# wled-tube.net
KiCad netlist of a schematic drawn in Altium Designer
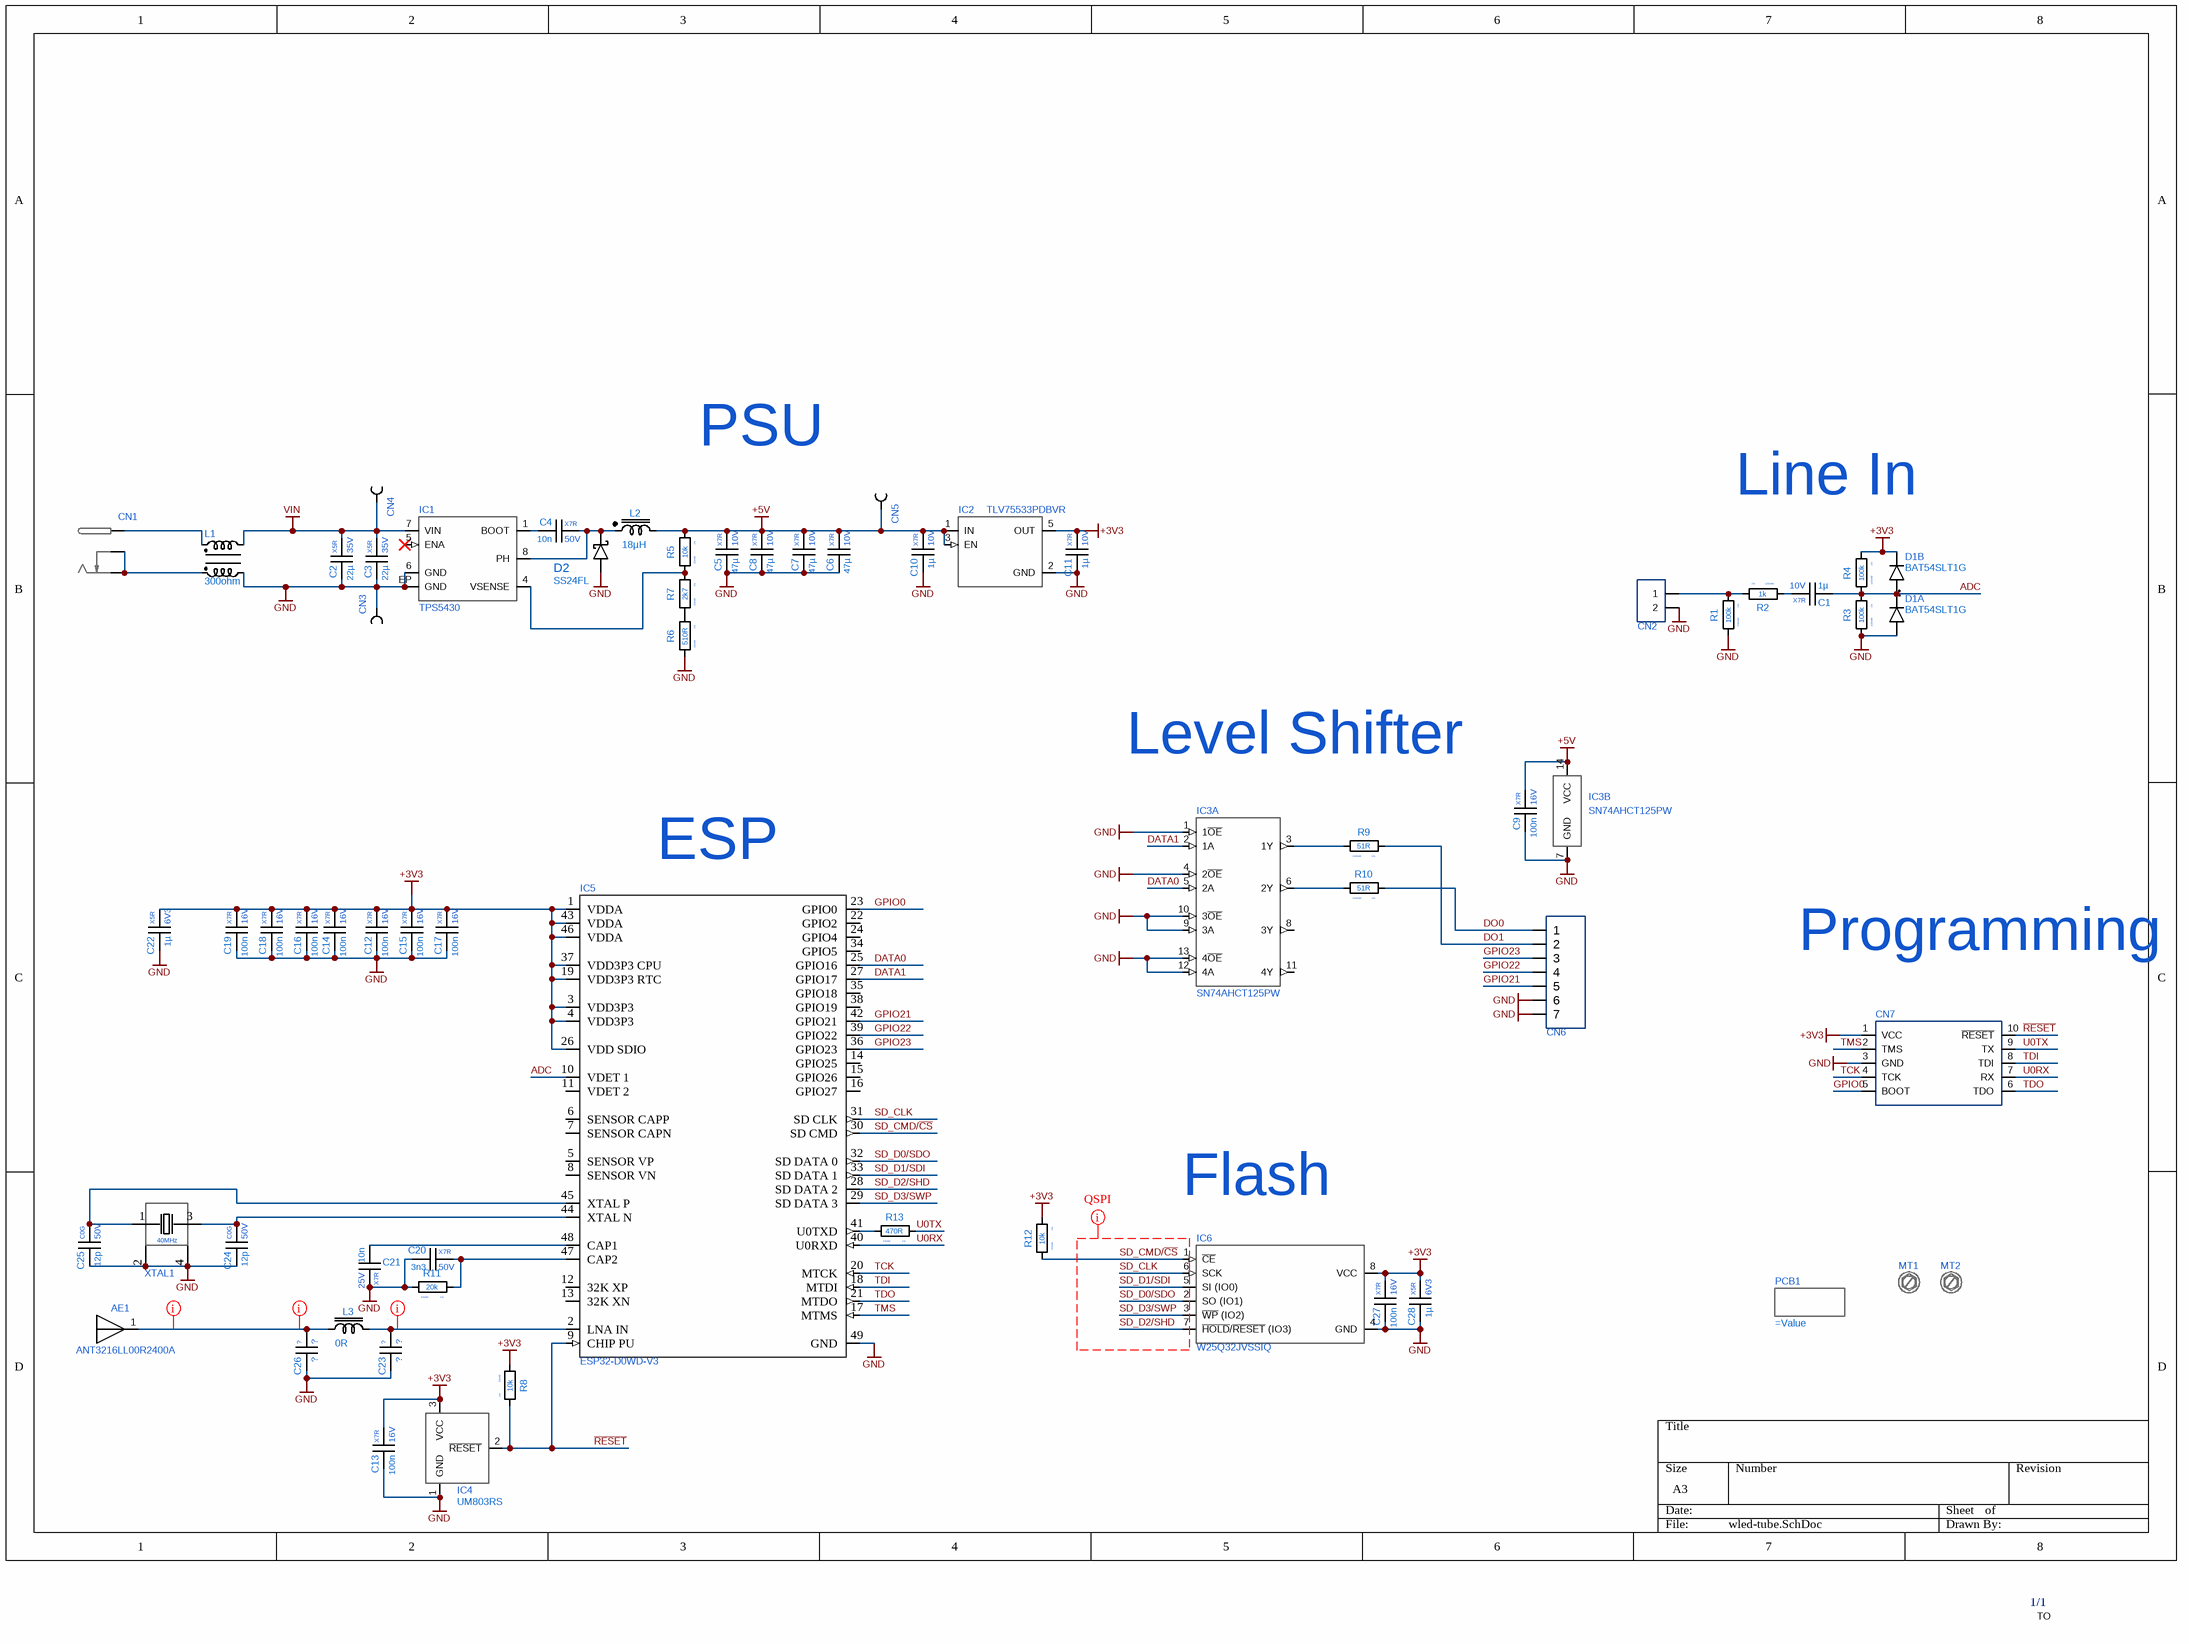
[diagram p0: wled-tube.SchDoc]

(export (version "E")
  (design (tool "Eeschema 10.0.6"))
  (components
    (comp (ref "AE1")
      (value "ANT3216LL00R2400A")
      (footprint "1206-ANT")
      (description "Ceramic chip antenna 2.4 GHz")
      (fields (field (name "MANUFACTURER") "Yageo"))
      (libsource (lib "RASE") (part "ANTENNA"))
    )
    (comp (ref "C1")
      (value "1µ")
      (footprint "0603-CAP")
      (description "CAP 0603 CERAMIC 1µ 10V ±10% X7R")
      (fields
        (field (name "_P2") "X7R")
        (field (name "_P1") "10V")
        (field (name "VOLTAGE") "10V")
        (field (name "TOLERANCE") "10%")
        (field (name "LIBRARY PATH") "NONPCAP.SchLib")
      )
      (libsource (lib "CDB") (part "NONPCAP"))
    )
    (comp (ref "C2")
      (value "22µ")
      (footprint "1210-CAP")
      (description "CAP 1210 CERAMIC 22µ 35V ±10% X5R")
      (fields
        (field (name "_P2") "X5R")
        (field (name "_P1") "35V")
        (field (name "VOLTAGE") "35V")
        (field (name "TOLERANCE") "10%")
        (field (name "LIBRARY PATH") "NONPCAP.SchLib")
      )
      (libsource (lib "CDB") (part "NONPCAP"))
    )
    (comp (ref "C3")
      (value "22µ")
      (footprint "1210-CAP")
      (description "CAP 1210 CERAMIC 22µ 35V ±10% X5R")
      (fields
        (field (name "_P2") "X5R")
        (field (name "_P1") "35V")
        (field (name "VOLTAGE") "35V")
        (field (name "TOLERANCE") "10%")
        (field (name "LIBRARY PATH") "NONPCAP.SchLib")
      )
      (libsource (lib "CDB") (part "NONPCAP"))
    )
    (comp (ref "C4")
      (value "10n")
      (footprint "0603-CAP")
      (description "CAP 0603 CERAMIC 10n 50V ±10% X7R")
      (fields
        (field (name "_P2") "X7R")
        (field (name "_P1") "50V")
        (field (name "VOLTAGE") "50V")
        (field (name "TOLERANCE") "10%")
        (field (name "LIBRARY PATH") "NONPCAP.SchLib")
      )
      (libsource (lib "CDB") (part "NONPCAP"))
    )
    (comp (ref "C5")
      (value "47µ")
      (footprint "1210-CAP")
      (description "CAP 1210 CERAMIC 47µ 10V ±10% X7R")
      (fields
        (field (name "_P2") "X7R")
        (field (name "_P1") "10V")
        (field (name "VOLTAGE") "10V")
        (field (name "TOLERANCE") "10%")
        (field (name "LIBRARY PATH") "NONPCAP.SchLib")
      )
      (libsource (lib "CDB") (part "NONPCAP"))
    )
    (comp (ref "C6")
      (value "47µ")
      (footprint "1210-CAP")
      (description "CAP 1210 CERAMIC 47µ 10V ±10% X7R")
      (fields
        (field (name "_P2") "X7R")
        (field (name "_P1") "10V")
        (field (name "VOLTAGE") "10V")
        (field (name "TOLERANCE") "10%")
        (field (name "LIBRARY PATH") "NONPCAP.SchLib")
      )
      (libsource (lib "CDB") (part "NONPCAP"))
    )
    (comp (ref "C7")
      (value "47µ")
      (footprint "1210-CAP")
      (description "CAP 1210 CERAMIC 47µ 10V ±10% X7R")
      (fields
        (field (name "_P2") "X7R")
        (field (name "_P1") "10V")
        (field (name "VOLTAGE") "10V")
        (field (name "TOLERANCE") "10%")
        (field (name "LIBRARY PATH") "NONPCAP.SchLib")
      )
      (libsource (lib "CDB") (part "NONPCAP"))
    )
    (comp (ref "C8")
      (value "47µ")
      (footprint "1210-CAP")
      (description "CAP 1210 CERAMIC 47µ 10V ±10% X7R")
      (fields
        (field (name "_P2") "X7R")
        (field (name "_P1") "10V")
        (field (name "VOLTAGE") "10V")
        (field (name "TOLERANCE") "10%")
        (field (name "LIBRARY PATH") "NONPCAP.SchLib")
      )
      (libsource (lib "CDB") (part "NONPCAP"))
    )
    (comp (ref "C9")
      (value "100n")
      (footprint "0402-CAP")
      (description "CAP 0402 CERAMIC 100n 16V ±10% X7R")
      (fields
        (field (name "_P2") "X7R")
        (field (name "_P1") "16V")
        (field (name "TOLERANCE") "10%")
        (field (name "VOLTAGE") "16V")
        (field (name "LIBRARY PATH") "NONPCAP.SchLib")
      )
      (libsource (lib "CDB") (part "NONPCAP"))
    )
    (comp (ref "C10")
      (value "1µ")
      (footprint "0603-CAP")
      (description "CAP 0603 CERAMIC 1µ 10V ±10% X7R")
      (fields
        (field (name "_P2") "X7R")
        (field (name "_P1") "10V")
        (field (name "VOLTAGE") "10V")
        (field (name "TOLERANCE") "10%")
        (field (name "LIBRARY PATH") "NONPCAP.SchLib")
      )
      (libsource (lib "CDB") (part "NONPCAP"))
    )
    (comp (ref "C11")
      (value "1µ")
      (footprint "0603-CAP")
      (description "CAP 0603 CERAMIC 1µ 10V ±10% X7R")
      (fields
        (field (name "_P2") "X7R")
        (field (name "_P1") "10V")
        (field (name "VOLTAGE") "10V")
        (field (name "TOLERANCE") "10%")
        (field (name "LIBRARY PATH") "NONPCAP.SchLib")
      )
      (libsource (lib "CDB") (part "NONPCAP"))
    )
    (comp (ref "C12")
      (value "100n")
      (footprint "0402-CAP")
      (description "CAP 0402 CERAMIC 100n 16V ±10% X7R")
      (fields
        (field (name "_P2") "X7R")
        (field (name "_P1") "16V")
        (field (name "TOLERANCE") "10%")
        (field (name "VOLTAGE") "16V")
        (field (name "LIBRARY PATH") "NONPCAP.SchLib")
      )
      (libsource (lib "CDB") (part "NONPCAP"))
    )
    (comp (ref "C13")
      (value "100n")
      (footprint "0402-CAP")
      (description "CAP 0402 CERAMIC 100n 16V ±10% X7R")
      (fields
        (field (name "_P2") "X7R")
        (field (name "_P1") "16V")
        (field (name "TOLERANCE") "10%")
        (field (name "VOLTAGE") "16V")
        (field (name "LIBRARY PATH") "NONPCAP.SchLib")
      )
      (libsource (lib "CDB") (part "NONPCAP"))
    )
    (comp (ref "C14")
      (value "100n")
      (footprint "0402-CAP")
      (description "CAP 0402 CERAMIC 100n 16V ±10% X7R")
      (fields
        (field (name "_P2") "X7R")
        (field (name "_P1") "16V")
        (field (name "TOLERANCE") "10%")
        (field (name "VOLTAGE") "16V")
        (field (name "LIBRARY PATH") "NONPCAP.SchLib")
      )
      (libsource (lib "CDB") (part "NONPCAP"))
    )
    (comp (ref "C15")
      (value "100n")
      (footprint "0402-CAP")
      (description "CAP 0402 CERAMIC 100n 16V ±10% X7R")
      (fields
        (field (name "_P2") "X7R")
        (field (name "_P1") "16V")
        (field (name "TOLERANCE") "10%")
        (field (name "VOLTAGE") "16V")
        (field (name "LIBRARY PATH") "NONPCAP.SchLib")
      )
      (libsource (lib "CDB") (part "NONPCAP"))
    )
    (comp (ref "C16")
      (value "100n")
      (footprint "0402-CAP")
      (description "CAP 0402 CERAMIC 100n 16V ±10% X7R")
      (fields
        (field (name "_P2") "X7R")
        (field (name "_P1") "16V")
        (field (name "TOLERANCE") "10%")
        (field (name "VOLTAGE") "16V")
        (field (name "LIBRARY PATH") "NONPCAP.SchLib")
      )
      (libsource (lib "CDB") (part "NONPCAP"))
    )
    (comp (ref "C17")
      (value "100n")
      (footprint "0402-CAP")
      (description "CAP 0402 CERAMIC 100n 16V ±10% X7R")
      (fields
        (field (name "_P2") "X7R")
        (field (name "_P1") "16V")
        (field (name "TOLERANCE") "10%")
        (field (name "VOLTAGE") "16V")
        (field (name "LIBRARY PATH") "NONPCAP.SchLib")
      )
      (libsource (lib "CDB") (part "NONPCAP"))
    )
    (comp (ref "C18")
      (value "100n")
      (footprint "0402-CAP")
      (description "CAP 0402 CERAMIC 100n 16V ±10% X7R")
      (fields
        (field (name "_P2") "X7R")
        (field (name "_P1") "16V")
        (field (name "TOLERANCE") "10%")
        (field (name "VOLTAGE") "16V")
        (field (name "LIBRARY PATH") "NONPCAP.SchLib")
      )
      (libsource (lib "CDB") (part "NONPCAP"))
    )
    (comp (ref "C19")
      (value "100n")
      (footprint "0402-CAP")
      (description "CAP 0402 CERAMIC 100n 16V ±10% X7R")
      (fields
        (field (name "_P2") "X7R")
        (field (name "_P1") "16V")
        (field (name "TOLERANCE") "10%")
        (field (name "VOLTAGE") "16V")
        (field (name "LIBRARY PATH") "NONPCAP.SchLib")
      )
      (libsource (lib "CDB") (part "NONPCAP"))
    )
    (comp (ref "C20")
      (value "3n3")
      (footprint "0402-CAP")
      (description "Cap SMT 0402 3n3 50V X7R ±10%")
      (fields
        (field (name "_P2") "X7R")
        (field (name "_P1") "50V")
        (field (name "VOLTAGE") "50V")
        (field (name "TOLERANCE") "10%")
      )
      (libsource (lib "RASE") (part "NPCAP"))
    )
    (comp (ref "C21")
      (value "10n")
      (footprint "0402-CAP")
      (description "Cap SMT 0402 10n 25V X7R ±10%")
      (fields
        (field (name "VOLTAGE") "25V")
        (field (name "TOLERANCE") "10%")
        (field (name "_P2") "X7R")
        (field (name "_P1") "25V")
      )
      (libsource (lib "RASE") (part "NPCAP"))
    )
    (comp (ref "C22")
      (value "1µ")
      (footprint "0402-CAP")
      (description "CAP 0402 CERAMIC 1µ 6V3 ±10% X5R")
      (fields
        (field (name "_P2") "X5R")
        (field (name "_P1") "6V3")
        (field (name "TOLERANCE") "10%")
        (field (name "VOLTAGE") "6V3")
        (field (name "LIBRARY PATH") "NONPCAP.SchLib")
      )
      (libsource (lib "CDB") (part "NONPCAP"))
    )
    (comp (ref "C23")
      (value "?")
      (footprint "0402-CAP")
      (description "Cap SMT 0402 ? ? ? ±?%")
      (fields (field (name "_P2") "?") (field (name "_P1") "?") (field (name "TOLERANCE") "?%"))
      (libsource (lib "RASE") (part "NPCAP"))
    )
    (comp (ref "C24")
      (value "12p")
      (footprint "0402-CAP")
      (description "Cap SMT 0402 12p 50V C0G ±5%")
      (fields
        (field (name "_P2") "C0G")
        (field (name "_P1") "50V")
        (field (name "VOLTAGE") "50V")
        (field (name "TOLERANCE") "5%")
      )
      (libsource (lib "RASE") (part "NPCAP"))
    )
    (comp (ref "C25")
      (value "12p")
      (footprint "0402-CAP")
      (description "Cap SMT 0402 12p 50V C0G ±5%")
      (fields
        (field (name "_P2") "C0G")
        (field (name "_P1") "50V")
        (field (name "VOLTAGE") "50V")
        (field (name "TOLERANCE") "5%")
      )
      (libsource (lib "RASE") (part "NPCAP"))
    )
    (comp (ref "C26")
      (value "?")
      (footprint "0402-CAP")
      (description "Cap SMT 0402 ? ? ? ±?%")
      (fields (field (name "_P2") "?") (field (name "_P1") "?") (field (name "TOLERANCE") "?%"))
      (libsource (lib "RASE") (part "NPCAP"))
    )
    (comp (ref "C27")
      (value "100n")
      (footprint "0402-CAP")
      (description "CAP 0402 CERAMIC 100n 16V ±10% X7R")
      (fields
        (field (name "_P2") "X7R")
        (field (name "_P1") "16V")
        (field (name "TOLERANCE") "10%")
        (field (name "VOLTAGE") "16V")
        (field (name "LIBRARY PATH") "NONPCAP.SchLib")
      )
      (libsource (lib "CDB") (part "NONPCAP"))
    )
    (comp (ref "C28")
      (value "1µ")
      (footprint "0402-CAP")
      (description "CAP 0402 CERAMIC 1µ 6V3 ±10% X5R")
      (fields
        (field (name "_P2") "X5R")
        (field (name "_P1") "6V3")
        (field (name "TOLERANCE") "10%")
        (field (name "VOLTAGE") "6V3")
        (field (name "LIBRARY PATH") "NONPCAP.SchLib")
      )
      (libsource (lib "CDB") (part "NONPCAP"))
    )
    (comp (ref "CN1")
      (value "~")
      (footprint "DCJACK-1")
      (description "DC Jack Lih Sheng LD-0202A 2.0mm")
      (fields
        (field (name "MANUFACTURER") "Lih Sheng")
        (field (name "MANUFACTURER PART NUMBER") "LD-0202A-2.0")
      )
      (libsource (lib "CDB") (part "DCJACK-1"))
    )
    (comp (ref "CN2")
      (value "CON-HDR-MALE-2.54MM-1x2-VERT-THT")
      (footprint "CON-HDR-MALE-2.54MM-1x2-VERT-THT")
      (description "CONN HEADER VERT 2POS 2.54MM")
      (fields
        (field (name "MANUFACTURER PART NUMBER") "TSW-102-07-L-S")
        (field (name "MANUFACTURER") "Samtec Inc.")
      )
      (libsource (lib "CDB") (part "CON-1x2"))
    )
    (comp (ref "CN3") (value "PAD1.3MM") (footprint "PAD1MM3") (libsource (lib "CDB") (part "PAD1.3MM")))
    (comp (ref "CN4") (value "PAD1.3MM") (footprint "PAD1MM3") (libsource (lib "CDB") (part "PAD1.3MM")))
    (comp (ref "CN5") (value "PAD1.3MM") (footprint "PAD1MM3") (libsource (lib "CDB") (part "PAD1.3MM")))
    (comp (ref "CN6")
      (value "CON-HDR-MALE-2.54MM-1x7-VERT-THT")
      (footprint "CON-HDR-MALE-2.54MM-1x7-VERT-THT")
      (description "CONN HEADER VERT 7POS 2.54MM")
      (fields
        (field (name "MANUFACTURER PART NUMBER") "TSW-107-07-L-S")
        (field (name "MANUFACTURER") "Samtec Inc.")
      )
      (libsource (lib "CDB") (part "CON-1x7"))
    )
    (comp (ref "CN7")
      (value "TC2050_RASE")
      (footprint "TC2050")
      (description "Solderless programming connector, mates with Tag-Connect TC2050")
      (libsource (lib "RASE") (part "TC2050_RASE"))
    )
    (comp (ref "D1")
      (value "BAT54SLT1G")
      (footprint "SOT-23")
      (description "BAT54SLT1G Dual 30V 200mA Schottky Diode")
      (fields (field (name "MANUFACTURER") "ON Semiconductor"))
      (libsource (lib "CDB") (part "BAT54SLT1G"))
    )
    (comp (ref "D2")
      (value "SS24FL")
      (footprint "SMAF")
      (description "40V 550mV@2A 2A SMAF Schottky Barrier Diodes (SBD) ROHS")
      (fields (field (name "MANUFACTURER") "Shikues"))
      (libsource (lib "RASE") (part "DiodeS"))
    )
    (comp (ref "IC1")
      (value "TPS5430")
      (footprint "TPS5430")
      (description "Step-down type SO-8 DC-DC Converters ROHS")
      (fields (field (name "MANUFACTURER PART NUMBER") "TPS5430DDAR") (field (name "MANUFACTURER") "TI"))
      (libsource (lib "RASE") (part "TPS5430"))
    )
    (comp (ref "IC2")
      (value "TLV75533PDBVR")
      (footprint "SOT-23-5")
      (fields (field (name "MANUFACTURER") "TI"))
      (libsource (lib "CDB") (part "DS8241-33S5"))
    )
    (comp (ref "IC3")
      (value "SN74AHCT125PW")
      (footprint "TSSOP14")
      (description "Quad buffer, TSSOP14")
      (fields
        (field (name "MANUFACTURER") "Texas Instruments")
        (field (name "MANUFACTURER PART NUMBER") "SN74AHCT125PWR")
      )
      (libsource (lib "CDB") (part "74AHCT125PW"))
    )
    (comp (ref "IC4")
      (value "UM803RS")
      (footprint "SOT-23")
      (description "MICROPROCESSOR RESET CIRCUIT 2.63V SOT23")
      (libsource (lib "CDB") (part "UM803RS"))
    )
    (comp (ref "IC5")
      (value "ESP32-D0WD-V3")
      (footprint "ESP32-D0WD-V3")
      (fields (field (name "MANUFACTURER") "Espressif"))
      (libsource (lib "RASE") (part "ESP32-D0WD-V3"))
    )
    (comp (ref "IC6")
      (value "W25Q32JVSSIQ")
      (footprint "SO-08L")
      (description "3V 32M-BIT SERIAL FLASH MEMORY WITH DUAL/QUAD SPI, QPI & DTR")
      (fields (field (name "MANUFACTURER") "Winbond"))
      (libsource (lib "CDB") (part "IS25LP032D-JBLE"))
    )
    (comp (ref "L1")
      (value "300ohm")
      (footprint "COILCMACM7060")
      (description "TDK ACM7060 / Sunltech Tech SMW7060 / Shun Xiang Nuo Elec SMCM7060")
      (fields
        (field (name "MANUFACTURER") "TDK, Sunltech, Shun Xiang Nuo Elec")
        (field (name "MANUFACTURER PART NUMBER") "ACM7060-301-2PL-TL01, SMW7060S301NTT, SMCM7060-301T")
      )
      (libsource (lib "CDB") (part "COILCM7060-"))
    )
    (comp (ref "L2")
      (value "18µH")
      (footprint "COILSRN8040")
      (description "18uH, 68mOhm(max), 2.7A(sat), 2.4A(DC)")
      (fields (field (name "MANUFACTURER") "SXN") (field (name "MANUFACTURER PART NUMBER") "SMNR8040-180MT"))
      (libsource (lib "CDB") (part "COIL_DOTTED"))
    )
    (comp (ref "L3")
      (value "0R")
      (footprint "0402-IND")
      (description "Inductor SMT ? ±?%")
      (fields (field (name "TOLERANCE") "?%"))
      (libsource (lib "RASE") (part "COIL"))
    )
    (comp (ref "MT1") (value "*") (footprint "SCRW3MM") (libsource (lib "CDB") (part "SCRW-3MMISO")))
    (comp (ref "MT2") (value "*") (footprint "SCRW3MM") (libsource (lib "CDB") (part "SCRW-3MMISO")))
    (comp (ref "PCB1")
      (value "~")
      (footprint "PCB")
      (description "See PCB gerber files for specifications.")
      (libsource (lib "CDB") (part "PCB"))
    )
    (comp (ref "R1")
      (value "100k")
      (footprint "0603-RES")
      (description "RES SMD 100K OHM 1% 1/10W 0603")
      (fields
        (field (name "_P2") "1%")
        (field (name "_P1") "100mW")
        (field (name "MANUFACTURER PART NUMBER") "RC0603FR-07100KL")
        (field (name "MANUFACTURER") "Yageo")
      )
      (libsource (lib "CDB") (part "RES"))
    )
    (comp (ref "R2")
      (value "1k")
      (footprint "0603-RES")
      (description "RES SMD 1K OHM 1% 1/10W 0603")
      (fields
        (field (name "_P2") "1%")
        (field (name "_P1") "100mW")
        (field (name "MANUFACTURER PART NUMBER") "RC0603FR-071KL")
        (field (name "MANUFACTURER") "Yageo")
      )
      (libsource (lib "CDB") (part "RES"))
    )
    (comp (ref "R3")
      (value "100k")
      (footprint "0603-RES")
      (description "RES SMD 100K OHM 1% 1/10W 0603")
      (fields
        (field (name "_P2") "1%")
        (field (name "_P1") "100mW")
        (field (name "MANUFACTURER PART NUMBER") "RC0603FR-07100KL")
        (field (name "MANUFACTURER") "Yageo")
      )
      (libsource (lib "CDB") (part "RES"))
    )
    (comp (ref "R4")
      (value "100k")
      (footprint "0603-RES")
      (description "RES SMD 100K OHM 1% 1/10W 0603")
      (fields
        (field (name "_P2") "1%")
        (field (name "_P1") "100mW")
        (field (name "MANUFACTURER PART NUMBER") "RC0603FR-07100KL")
        (field (name "MANUFACTURER") "Yageo")
      )
      (libsource (lib "CDB") (part "RES"))
    )
    (comp (ref "R5")
      (value "10k")
      (footprint "0402-RES")
      (description "RES SMD 10K OHM 1% 1/16W 0402")
      (fields
        (field (name "_P2") "1%")
        (field (name "_P1") "63mW")
        (field (name "MANUFACTURER PART NUMBER") "RC0402FR-0710KL")
        (field (name "MANUFACTURER") "Yageo")
      )
      (libsource (lib "CDB") (part "RES"))
    )
    (comp (ref "R6")
      (value "510R")
      (footprint "0402-RES")
      (description "RES SMD 510 OHM 1% 1/16W 0402")
      (fields
        (field (name "_P2") "1%")
        (field (name "_P1") "63mW")
        (field (name "MANUFACTURER PART NUMBER") "RC0402FR-07510RL")
        (field (name "MANUFACTURER") "Yageo")
      )
      (libsource (lib "CDB") (part "RES"))
    )
    (comp (ref "R7")
      (value "2k7")
      (footprint "0402-RES")
      (description "RES SMD 2.7K OHM 1% 1/16W 0402")
      (fields
        (field (name "_P2") "1%")
        (field (name "_P1") "63mW")
        (field (name "MANUFACTURER PART NUMBER") "RC0402FR-072K7L")
        (field (name "MANUFACTURER") "Yageo")
      )
      (libsource (lib "CDB") (part "RES"))
    )
    (comp (ref "R8")
      (value "10k")
      (footprint "0402-RES")
      (description "RES SMD 10K OHM 1% 1/16W 0402")
      (fields
        (field (name "_P2") "1%")
        (field (name "_P1") "63mW")
        (field (name "MANUFACTURER PART NUMBER") "RC0402FR-0710KL")
        (field (name "MANUFACTURER") "Yageo")
      )
      (libsource (lib "") (part "RES_1"))
    )
    (comp (ref "R9")
      (value "51R")
      (footprint "0603-RES")
      (description "RES SMD 51 OHM 1% 1/10W 0603")
      (fields
        (field (name "_P2") "1%")
        (field (name "_P1") "100mW")
        (field (name "MANUFACTURER PART NUMBER") "RC0603FR-0751RL")
        (field (name "MANUFACTURER") "Yageo")
      )
      (libsource (lib "") (part "RES_1"))
    )
    (comp (ref "R10")
      (value "51R")
      (footprint "0603-RES")
      (description "RES SMD 51 OHM 1% 1/10W 0603")
      (fields
        (field (name "_P2") "1%")
        (field (name "_P1") "100mW")
        (field (name "MANUFACTURER PART NUMBER") "RC0603FR-0751RL")
        (field (name "MANUFACTURER") "Yageo")
      )
      (libsource (lib "") (part "RES_1"))
    )
    (comp (ref "R11")
      (value "20k")
      (footprint "0402-RES")
      (description "RES SMD 20K OHM 1% 1/16W 0402")
      (fields
        (field (name "_P2") "1%")
        (field (name "_P1") "63mW")
        (field (name "MANUFACTURER PART NUMBER") "RC0402FR-0720KL")
        (field (name "MANUFACTURER") "Yageo")
      )
      (libsource (lib "") (part "RES_1"))
    )
    (comp (ref "R12")
      (value "10k")
      (footprint "0402-RES")
      (description "RES SMD 10K OHM 1% 1/16W 0402")
      (fields
        (field (name "_P2") "1%")
        (field (name "_P1") "63mW")
        (field (name "MANUFACTURER PART NUMBER") "RC0402FR-0710KL")
        (field (name "MANUFACTURER") "Yageo")
      )
      (libsource (lib "CDB") (part "RES"))
    )
    (comp (ref "R13")
      (value "470R")
      (footprint "0402-RES")
      (description "RES SMD 470 OHM 1% 1/16W 0402")
      (fields
        (field (name "_P2") "1%")
        (field (name "_P1") "63mW")
        (field (name "MANUFACTURER PART NUMBER") "RC0402FR-07470RL")
        (field (name "MANUFACTURER") "Yageo")
      )
      (libsource (lib "") (part "RES_1"))
    )
    (comp (ref "XTAL1")
      (value "TSX-3225 40.0000MF10Y-K0")
      (footprint "TSX-3225")
      (description "CRYSTAL 40.0000MHZ 10PF SMD")
      (fields (field (name "FREQUENCY") "40MHz") (field (name "MANUFACTURER") "EPSON"))
      (libsource (lib "CDB") (part "TSX-3225"))
    )
  )
  (nets
    (net (code "1") (name "+3V3") (class "Default")
      (node (ref "C11") (pin "2") (pinfunction "2_2") (pintype "passive"))
      (node (ref "C12") (pin "2") (pinfunction "2_2") (pintype "passive"))
      (node (ref "C13") (pin "2") (pinfunction "2_2") (pintype "passive"))
      (node (ref "C14") (pin "2") (pinfunction "2_2") (pintype "passive"))
      (node (ref "C15") (pin "2") (pinfunction "2_2") (pintype "passive"))
      (node (ref "C16") (pin "2") (pinfunction "2_2") (pintype "passive"))
      (node (ref "C17") (pin "2") (pinfunction "2_2") (pintype "passive"))
      (node (ref "C18") (pin "2") (pinfunction "2_2") (pintype "passive"))
      (node (ref "C19") (pin "2") (pinfunction "2_2") (pintype "passive"))
      (node (ref "C22") (pin "2") (pinfunction "2_2") (pintype "passive"))
      (node (ref "C27") (pin "2") (pinfunction "2_2") (pintype "passive"))
      (node (ref "C28") (pin "2") (pinfunction "2_2") (pintype "passive"))
      (node (ref "CN7") (pin "1") (pinfunction "VCC_1") (pintype "passive"))
      (node (ref "D1") (pin "2") (pinfunction "K_2") (pintype "passive"))
      (node (ref "IC2") (pin "5") (pinfunction "OUT_5") (pintype "power_in"))
      (node (ref "IC4") (pin "3") (pinfunction "VCC_3") (pintype "passive"))
      (node (ref "IC5") (pin "1") (pinfunction "VDDA_1") (pintype "power_in"))
      (node (ref "IC5") (pin "19") (pinfunction "VDD3P3_RTC_19") (pintype "power_in"))
      (node (ref "IC5") (pin "26") (pinfunction "VDD_SDIO_26") (pintype "power_in"))
      (node (ref "IC5") (pin "3") (pinfunction "VDD3P3_3") (pintype "power_in"))
      (node (ref "IC5") (pin "37") (pinfunction "VDD3P3_CPU_37") (pintype "power_in"))
      (node (ref "IC5") (pin "4") (pinfunction "VDD3P3_4") (pintype "power_in"))
      (node (ref "IC5") (pin "43") (pinfunction "VDDA_43") (pintype "power_in"))
      (node (ref "IC5") (pin "46") (pinfunction "VDDA_46") (pintype "power_in"))
      (node (ref "IC6") (pin "8") (pinfunction "VCC_8") (pintype "power_in"))
      (node (ref "R12") (pin "2") (pinfunction "2_2") (pintype "passive"))
      (node (ref "R4") (pin "2") (pinfunction "2_2") (pintype "passive"))
      (node (ref "R8") (pin "1") (pinfunction "1_1") (pintype "passive"))
    )
    (net (code "2") (name "+5V") (class "Default")
      (node (ref "C10") (pin "2") (pinfunction "2_2") (pintype "passive"))
      (node (ref "C5") (pin "2") (pinfunction "2_2") (pintype "passive"))
      (node (ref "C6") (pin "2") (pinfunction "2_2") (pintype "passive"))
      (node (ref "C7") (pin "2") (pinfunction "2_2") (pintype "passive"))
      (node (ref "C8") (pin "2") (pinfunction "2_2") (pintype "passive"))
      (node (ref "C9") (pin "2") (pinfunction "2_2") (pintype "passive"))
      (node (ref "CN5") (pin "1") (pinfunction "1_1") (pintype "passive"))
      (node (ref "IC2") (pin "1") (pinfunction "IN_1") (pintype "power_in"))
      (node (ref "IC2") (pin "3") (pinfunction "EN_3") (pintype "input"))
      (node (ref "IC3") (pin "14") (pinfunction "VCC_14") (pintype "power_in"))
      (node (ref "L2") (pin "2") (pinfunction "2_2") (pintype "passive"))
      (node (ref "R5") (pin "2") (pinfunction "2_2") (pintype "passive"))
    )
    (net (code "3") (name "/ADC") (class "Default")
      (node (ref "C1") (pin "1") (pinfunction "1_1") (pintype "passive"))
      (node (ref "D1") (pin "3") (pinfunction "K_3") (pintype "passive"))
      (node (ref "IC5") (pin "10") (pinfunction "VDET_1_10") (pintype "power_in"))
      (node (ref "R3") (pin "2") (pinfunction "2_2") (pintype "passive"))
      (node (ref "R4") (pin "1") (pinfunction "1_1") (pintype "passive"))
    )
    (net (code "4") (name "/DATA0") (class "Default")
      (node (ref "IC3") (pin "5") (pinfunction "2A_5") (pintype "input"))
      (node (ref "IC5") (pin "25") (pinfunction "GPIO16_25") (pintype "bidirectional"))
    )
    (net (code "5") (name "/DATA1") (class "Default")
      (node (ref "IC3") (pin "2") (pinfunction "1A_2") (pintype "input"))
      (node (ref "IC5") (pin "27") (pinfunction "GPIO17_27") (pintype "bidirectional"))
    )
    (net (code "6") (name "/DO0") (class "Default")
      (node (ref "CN6") (pin "1") (pinfunction "1_1") (pintype "passive"))
      (node (ref "R10") (pin "2") (pinfunction "2_2") (pintype "passive"))
    )
    (net (code "7") (name "/DO1") (class "Default")
      (node (ref "CN6") (pin "2") (pinfunction "2_2") (pintype "passive"))
      (node (ref "R9") (pin "2") (pinfunction "2_2") (pintype "passive"))
    )
    (net (code "8") (name "/GPIO0") (class "Default")
      (node (ref "CN7") (pin "5") (pinfunction "BOOT_5") (pintype "passive"))
      (node (ref "IC5") (pin "23") (pinfunction "GPIO0_23") (pintype "bidirectional"))
    )
    (net (code "9") (name "/GPIO21") (class "Default")
      (node (ref "CN6") (pin "5") (pinfunction "5_5") (pintype "passive"))
      (node (ref "IC5") (pin "42") (pinfunction "GPIO21_42") (pintype "bidirectional"))
    )
    (net (code "10") (name "/GPIO22") (class "Default")
      (node (ref "CN6") (pin "4") (pinfunction "4_4") (pintype "passive"))
      (node (ref "IC5") (pin "39") (pinfunction "GPIO22_39") (pintype "bidirectional"))
    )
    (net (code "11") (name "/GPIO23") (class "Default")
      (node (ref "CN6") (pin "3") (pinfunction "3_3") (pintype "passive"))
      (node (ref "IC5") (pin "36") (pinfunction "GPIO23_36") (pintype "bidirectional"))
    )
    (net (code "12") (name "/SD_CLK") (class "Default")
      (node (ref "IC5") (pin "31") (pinfunction "SD_CLK_31") (pintype "output"))
      (node (ref "IC6") (pin "6") (pinfunction "SCK_6") (pintype "input"))
    )
    (net (code "13") (name "/SD_CMD{slash}~{CS}") (class "Default")
      (node (ref "IC5") (pin "30") (pinfunction "SD_CMD_30") (pintype "output"))
      (node (ref "IC6") (pin "1") (pinfunction "~{CE}_1") (pintype "input"))
      (node (ref "R12") (pin "1") (pinfunction "1_1") (pintype "passive"))
    )
    (net (code "14") (name "/SD_D0{slash}SDO") (class "Default")
      (node (ref "IC5") (pin "32") (pinfunction "SD_DATA_0_32") (pintype "output"))
      (node (ref "IC6") (pin "2") (pinfunction "SO_(IO1)_2") (pintype "bidirectional"))
    )
    (net (code "15") (name "/SD_D1{slash}SDI") (class "Default")
      (node (ref "IC5") (pin "33") (pinfunction "SD_DATA_1_33") (pintype "output"))
      (node (ref "IC6") (pin "5") (pinfunction "SI_(IO0)_5") (pintype "bidirectional"))
    )
    (net (code "16") (name "/SD_D2{slash}SHD") (class "Default")
      (node (ref "IC5") (pin "28") (pinfunction "SD_DATA_2_28") (pintype "bidirectional"))
      (node (ref "IC6") (pin "7") (pinfunction "~{HOLD}/~{RESET}_(IO3)_7") (pintype "bidirectional"))
    )
    (net (code "17") (name "/SD_D3{slash}SWP") (class "Default")
      (node (ref "IC5") (pin "29") (pinfunction "SD_DATA_3_29") (pintype "bidirectional"))
      (node (ref "IC6") (pin "3") (pinfunction "~{WP}_(IO2)_3") (pintype "bidirectional"))
    )
    (net (code "18") (name "/TCK") (class "Default")
      (node (ref "CN7") (pin "4") (pinfunction "TCK_4") (pintype "passive"))
      (node (ref "IC5") (pin "20") (pinfunction "MTCK_20") (pintype "input"))
    )
    (net (code "19") (name "/TDI") (class "Default")
      (node (ref "CN7") (pin "8") (pinfunction "TDI_8") (pintype "passive"))
      (node (ref "IC5") (pin "18") (pinfunction "MTDI_18") (pintype "input"))
    )
    (net (code "20") (name "/TDO") (class "Default")
      (node (ref "CN7") (pin "6") (pinfunction "TDO_6") (pintype "passive"))
      (node (ref "IC5") (pin "21") (pinfunction "MTDO_21") (pintype "output"))
    )
    (net (code "21") (name "/TMS") (class "Default")
      (node (ref "CN7") (pin "2") (pinfunction "TMS_2") (pintype "passive"))
      (node (ref "IC5") (pin "17") (pinfunction "MTMS_17") (pintype "input"))
    )
    (net (code "22") (name "/U0RX") (class "Default")
      (node (ref "CN7") (pin "7") (pinfunction "RX_7") (pintype "passive"))
      (node (ref "IC5") (pin "40") (pinfunction "U0RXD_40") (pintype "input"))
    )
    (net (code "23") (name "/U0TX") (class "Default")
      (node (ref "CN7") (pin "9") (pinfunction "TX_9") (pintype "passive"))
      (node (ref "R13") (pin "2") (pinfunction "2_2") (pintype "passive"))
    )
    (net (code "24") (name "/~{RESET}") (class "Default")
      (node (ref "CN7") (pin "10") (pinfunction "~{RESET}_10") (pintype "passive"))
      (node (ref "IC4") (pin "2") (pinfunction "RESET_2") (pintype "passive"))
      (node (ref "IC5") (pin "9") (pinfunction "CHIP_PU_9") (pintype "input"))
      (node (ref "R8") (pin "2") (pinfunction "2_2") (pintype "passive"))
    )
    (net (code "25") (name "GND") (class "Default")
      (node (ref "C10") (pin "1") (pinfunction "1_1") (pintype "passive"))
      (node (ref "C11") (pin "1") (pinfunction "1_1") (pintype "passive"))
      (node (ref "C12") (pin "1") (pinfunction "1_1") (pintype "passive"))
      (node (ref "C13") (pin "1") (pinfunction "1_1") (pintype "passive"))
      (node (ref "C14") (pin "1") (pinfunction "1_1") (pintype "passive"))
      (node (ref "C15") (pin "1") (pinfunction "1_1") (pintype "passive"))
      (node (ref "C16") (pin "1") (pinfunction "1_1") (pintype "passive"))
      (node (ref "C17") (pin "1") (pinfunction "1_1") (pintype "passive"))
      (node (ref "C18") (pin "1") (pinfunction "1_1") (pintype "passive"))
      (node (ref "C19") (pin "1") (pinfunction "1_1") (pintype "passive"))
      (node (ref "C2") (pin "1") (pinfunction "1_1") (pintype "passive"))
      (node (ref "C20") (pin "1") (pinfunction "1_1") (pintype "passive"))
      (node (ref "C21") (pin "2") (pinfunction "2_2") (pintype "passive"))
      (node (ref "C22") (pin "1") (pinfunction "1_1") (pintype "passive"))
      (node (ref "C23") (pin "1") (pinfunction "1_1") (pintype "passive"))
      (node (ref "C24") (pin "1") (pinfunction "1_1") (pintype "passive"))
      (node (ref "C25") (pin "1") (pinfunction "1_1") (pintype "passive"))
      (node (ref "C26") (pin "1") (pinfunction "1_1") (pintype "passive"))
      (node (ref "C27") (pin "1") (pinfunction "1_1") (pintype "passive"))
      (node (ref "C28") (pin "1") (pinfunction "1_1") (pintype "passive"))
      (node (ref "C3") (pin "1") (pinfunction "1_1") (pintype "passive"))
      (node (ref "C5") (pin "1") (pinfunction "1_1") (pintype "passive"))
      (node (ref "C6") (pin "1") (pinfunction "1_1") (pintype "passive"))
      (node (ref "C7") (pin "1") (pinfunction "1_1") (pintype "passive"))
      (node (ref "C8") (pin "1") (pinfunction "1_1") (pintype "passive"))
      (node (ref "C9") (pin "1") (pinfunction "1_1") (pintype "passive"))
      (node (ref "CN2") (pin "2") (pinfunction "2_2") (pintype "passive"))
      (node (ref "CN3") (pin "1") (pinfunction "1_1") (pintype "passive"))
      (node (ref "CN6") (pin "6") (pinfunction "6_6") (pintype "passive"))
      (node (ref "CN6") (pin "7") (pinfunction "7_7") (pintype "passive"))
      (node (ref "CN7") (pin "3") (pinfunction "GND_3") (pintype "passive"))
      (node (ref "D1") (pin "1") (pinfunction "A_1") (pintype "passive"))
      (node (ref "D2") (pin "A") (pinfunction "A_A") (pintype "passive"))
      (node (ref "IC1") (pin "6") (pinfunction "GND_6") (pintype "power_in"))
      (node (ref "IC1") (pin "EP") (pinfunction "GND_EP") (pintype "passive"))
      (node (ref "IC2") (pin "2") (pinfunction "GND_2") (pintype "power_in"))
      (node (ref "IC3") (pin "1") (pinfunction "1~{OE}_1") (pintype "input"))
      (node (ref "IC3") (pin "10") (pinfunction "3~{OE}_10") (pintype "input"))
      (node (ref "IC3") (pin "12") (pinfunction "4A_12") (pintype "input"))
      (node (ref "IC3") (pin "13") (pinfunction "4~{OE}_13") (pintype "input"))
      (node (ref "IC3") (pin "4") (pinfunction "2~{OE}_4") (pintype "input"))
      (node (ref "IC3") (pin "7") (pinfunction "GND_7") (pintype "power_in"))
      (node (ref "IC3") (pin "9") (pinfunction "3A_9") (pintype "input"))
      (node (ref "IC4") (pin "1") (pinfunction "GND_1") (pintype "passive"))
      (node (ref "IC5") (pin "49") (pinfunction "GND_49") (pintype "power_in"))
      (node (ref "IC6") (pin "4") (pinfunction "GND_4") (pintype "power_in"))
      (node (ref "L1") (pin "4") (pinfunction "4_4") (pintype "passive"))
      (node (ref "R1") (pin "1") (pinfunction "1_1") (pintype "passive"))
      (node (ref "R11") (pin "1") (pinfunction "1_1") (pintype "passive"))
      (node (ref "R3") (pin "1") (pinfunction "1_1") (pintype "passive"))
      (node (ref "R6") (pin "1") (pinfunction "1_1") (pintype "passive"))
      (node (ref "XTAL1") (pin "2") (pinfunction "GND_2") (pintype "power_in"))
      (node (ref "XTAL1") (pin "4") (pinfunction "GND_4") (pintype "power_in"))
    )
    (net (code "26") (name "Net-(AE1-Pad1)") (class "Default")
      (node (ref "AE1") (pin "1") (pinfunction "1_1") (pintype "passive"))
      (node (ref "C26") (pin "2") (pinfunction "2_2") (pintype "passive"))
      (node (ref "L3") (pin "1") (pinfunction "1_1") (pintype "passive"))
    )
    (net (code "27") (name "Net-(C1-Pad2)") (class "Default")
      (node (ref "C1") (pin "2") (pinfunction "2_2") (pintype "passive"))
      (node (ref "R2") (pin "1") (pinfunction "1_1") (pintype "passive"))
    )
    (net (code "28") (name "Net-(CN1-Pad1)") (class "Default")
      (node (ref "CN1") (pin "1") (pinfunction "1_1") (pintype "passive"))
      (node (ref "L1") (pin "2") (pinfunction "2_2") (pintype "passive"))
    )
    (net (code "29") (name "Net-(CN1-Pad2)") (class "Default")
      (node (ref "CN1") (pin "2") (pinfunction "2_2") (pintype "passive"))
      (node (ref "CN1") (pin "3") (pinfunction "3_3") (pintype "passive"))
      (node (ref "L1") (pin "1") (pinfunction "1_1") (pintype "passive"))
    )
    (net (code "30") (name "Net-(CN2-Pad1)") (class "Default")
      (node (ref "CN2") (pin "1") (pinfunction "1_1") (pintype "passive"))
      (node (ref "R1") (pin "2") (pinfunction "2_2") (pintype "passive"))
      (node (ref "R2") (pin "2") (pinfunction "2_2") (pintype "passive"))
    )
    (net (code "31") (name "Net-(IC1-BOOT)") (class "Default")
      (node (ref "C4") (pin "1") (pinfunction "1_1") (pintype "passive"))
      (node (ref "IC1") (pin "1") (pinfunction "BOOT_1") (pintype "passive"))
    )
    (net (code "32") (name "Net-(IC1-PH)") (class "Default")
      (node (ref "C4") (pin "2") (pinfunction "2_2") (pintype "passive"))
      (node (ref "D2") (pin "K") (pinfunction "K_K") (pintype "passive"))
      (node (ref "IC1") (pin "8") (pinfunction "PH_8") (pintype "passive"))
      (node (ref "L2") (pin "1") (pinfunction "1_1") (pintype "passive"))
    )
    (net (code "33") (name "Net-(IC1-VSENSE)") (class "Default")
      (node (ref "IC1") (pin "4") (pinfunction "VSENSE_4") (pintype "passive"))
      (node (ref "R5") (pin "1") (pinfunction "1_1") (pintype "passive"))
      (node (ref "R7") (pin "2") (pinfunction "2_2") (pintype "passive"))
    )
    (net (code "34") (name "Net-(IC3A-1Y)") (class "Default")
      (node (ref "IC3") (pin "3") (pinfunction "1Y_3") (pintype "output"))
      (node (ref "R9") (pin "1") (pinfunction "1_1") (pintype "passive"))
    )
    (net (code "35") (name "Net-(IC3A-2Y)") (class "Default")
      (node (ref "IC3") (pin "6") (pinfunction "2Y_6") (pintype "output"))
      (node (ref "R10") (pin "1") (pinfunction "1_1") (pintype "passive"))
    )
    (net (code "36") (name "Net-(IC5-CAP1)") (class "Default")
      (node (ref "C21") (pin "1") (pinfunction "1_1") (pintype "passive"))
      (node (ref "IC5") (pin "48") (pinfunction "CAP1_48") (pintype "passive"))
    )
    (net (code "37") (name "Net-(IC5-CAP2)") (class "Default")
      (node (ref "C20") (pin "2") (pinfunction "2_2") (pintype "passive"))
      (node (ref "IC5") (pin "47") (pinfunction "CAP2_47") (pintype "passive"))
      (node (ref "R11") (pin "2") (pinfunction "2_2") (pintype "passive"))
    )
    (net (code "38") (name "Net-(IC5-LNA_IN)") (class "Default")
      (node (ref "C23") (pin "2") (pinfunction "2_2") (pintype "passive"))
      (node (ref "IC5") (pin "2") (pinfunction "LNA_IN_2") (pintype "bidirectional"))
      (node (ref "L3") (pin "2") (pinfunction "2_2") (pintype "passive"))
    )
    (net (code "39") (name "Net-(IC5-U0TXD)") (class "Default")
      (node (ref "IC5") (pin "41") (pinfunction "U0TXD_41") (pintype "output"))
      (node (ref "R13") (pin "1") (pinfunction "1_1") (pintype "passive"))
    )
    (net (code "40") (name "Net-(IC5-XTAL_N)") (class "Default")
      (node (ref "C24") (pin "2") (pinfunction "2_2") (pintype "passive"))
      (node (ref "IC5") (pin "44") (pinfunction "XTAL_N_44") (pintype "passive"))
      (node (ref "XTAL1") (pin "3") (pinfunction "X2_3") (pintype "passive"))
    )
    (net (code "41") (name "Net-(IC5-XTAL_P)") (class "Default")
      (node (ref "C25") (pin "2") (pinfunction "2_2") (pintype "passive"))
      (node (ref "IC5") (pin "45") (pinfunction "XTAL_P_45") (pintype "passive"))
      (node (ref "XTAL1") (pin "1") (pinfunction "X1_1") (pintype "passive"))
    )
    (net (code "42") (name "Net-(R6-Pad2)") (class "Default")
      (node (ref "R6") (pin "2") (pinfunction "2_2") (pintype "passive"))
      (node (ref "R7") (pin "1") (pinfunction "1_1") (pintype "passive"))
    )
    (net (code "43") (name "VIN") (class "Default")
      (node (ref "C2") (pin "2") (pinfunction "2_2") (pintype "passive"))
      (node (ref "C3") (pin "2") (pinfunction "2_2") (pintype "passive"))
      (node (ref "CN4") (pin "1") (pinfunction "1_1") (pintype "passive"))
      (node (ref "IC1") (pin "7") (pinfunction "VIN_7") (pintype "power_in"))
      (node (ref "L1") (pin "3") (pinfunction "3_3") (pintype "passive"))
    )
    (net (code "44") (name "unconnected-(IC1-ENA-Pad5)") (class "Default")
      (node (ref "IC1") (pin "5") (pinfunction "ENA_5") (pintype "input+no_connect"))
    )
    (net (code "45") (name "unconnected-(IC3A-3Y-Pad8)") (class "Default")
      (node (ref "IC3") (pin "8") (pinfunction "3Y_8") (pintype "output"))
    )
    (net (code "46") (name "unconnected-(IC3A-4Y-Pad11)") (class "Default")
      (node (ref "IC3") (pin "11") (pinfunction "4Y_11") (pintype "output"))
    )
    (net (code "47") (name "unconnected-(IC5-32K_XN-Pad13)") (class "Default")
      (node (ref "IC5") (pin "13") (pinfunction "32K_XN_13") (pintype "bidirectional"))
    )
    (net (code "48") (name "unconnected-(IC5-32K_XP-Pad12)") (class "Default")
      (node (ref "IC5") (pin "12") (pinfunction "32K_XP_12") (pintype "bidirectional"))
    )
    (net (code "49") (name "unconnected-(IC5-GPIO2-Pad22)") (class "Default")
      (node (ref "IC5") (pin "22") (pinfunction "GPIO2_22") (pintype "bidirectional"))
    )
    (net (code "50") (name "unconnected-(IC5-GPIO4-Pad24)") (class "Default")
      (node (ref "IC5") (pin "24") (pinfunction "GPIO4_24") (pintype "bidirectional"))
    )
    (net (code "51") (name "unconnected-(IC5-GPIO5-Pad34)") (class "Default")
      (node (ref "IC5") (pin "34") (pinfunction "GPIO5_34") (pintype "bidirectional"))
    )
    (net (code "52") (name "unconnected-(IC5-GPIO18-Pad35)") (class "Default")
      (node (ref "IC5") (pin "35") (pinfunction "GPIO18_35") (pintype "bidirectional"))
    )
    (net (code "53") (name "unconnected-(IC5-GPIO19-Pad38)") (class "Default")
      (node (ref "IC5") (pin "38") (pinfunction "GPIO19_38") (pintype "bidirectional"))
    )
    (net (code "54") (name "unconnected-(IC5-GPIO25-Pad14)") (class "Default")
      (node (ref "IC5") (pin "14") (pinfunction "GPIO25_14") (pintype "bidirectional"))
    )
    (net (code "55") (name "unconnected-(IC5-GPIO26-Pad15)") (class "Default")
      (node (ref "IC5") (pin "15") (pinfunction "GPIO26_15") (pintype "bidirectional"))
    )
    (net (code "56") (name "unconnected-(IC5-GPIO27-Pad16)") (class "Default")
      (node (ref "IC5") (pin "16") (pinfunction "GPIO27_16") (pintype "bidirectional"))
    )
    (net (code "57") (name "unconnected-(IC5-SENSOR_CAPN-Pad7)") (class "Default")
      (node (ref "IC5") (pin "7") (pinfunction "SENSOR_CAPN_7") (pintype "passive"))
    )
    (net (code "58") (name "unconnected-(IC5-SENSOR_CAPP-Pad6)") (class "Default")
      (node (ref "IC5") (pin "6") (pinfunction "SENSOR_CAPP_6") (pintype "passive"))
    )
    (net (code "59") (name "unconnected-(IC5-SENSOR_VN-Pad8)") (class "Default")
      (node (ref "IC5") (pin "8") (pinfunction "SENSOR_VN_8") (pintype "passive"))
    )
    (net (code "60") (name "unconnected-(IC5-SENSOR_VP-Pad5)") (class "Default")
      (node (ref "IC5") (pin "5") (pinfunction "SENSOR_VP_5") (pintype "passive"))
    )
    (net (code "61") (name "unconnected-(IC5-VDET_2-Pad11)") (class "Default")
      (node (ref "IC5") (pin "11") (pinfunction "VDET_2_11") (pintype "power_in"))
    )
  )
)
